# untitled.net
KiCad netlist of a schematic drawn in EAGLE
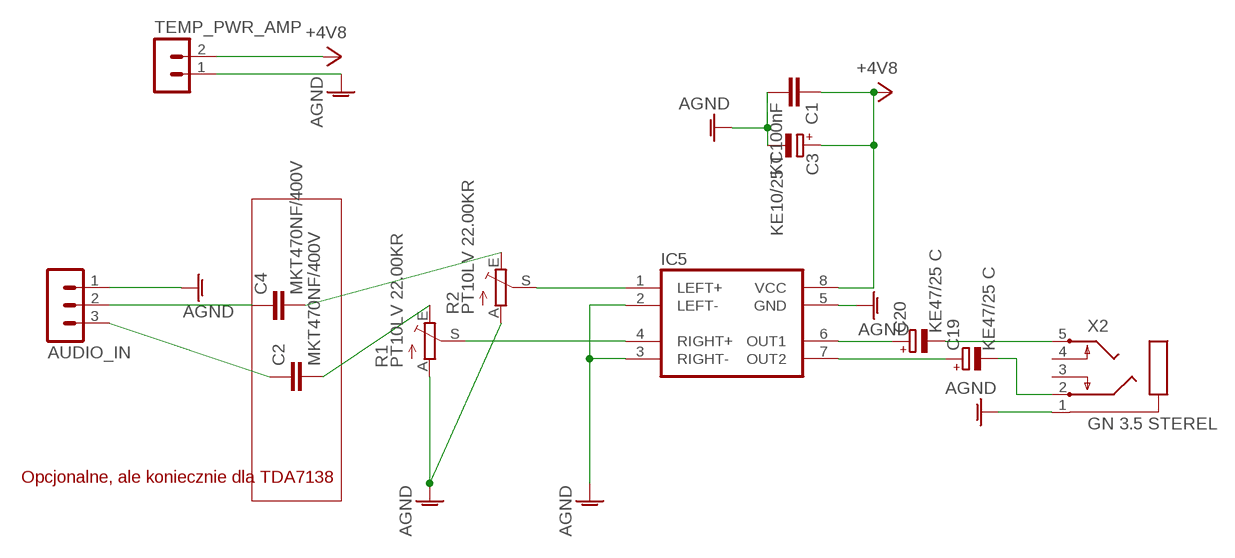
[diagram p0: schematic, sheet 1]

(export (version "E")
  (design (tool "Eeschema 10.0.6"))
  (components
    (comp (ref "AUDIO_IN")
      (value "MA03-1")
      (footprint "eagle-import:MA03-1")
      (fields (field (name "OC_FARNELL") "unknown") (field (name "OC_NEWARK") "unknown"))
      (libsource (lib "eagle-import") (part "MA03-1"))
    )
    (comp (ref "C1")
      (value "KC100nF")
      (footprint "eagle-import:C025-025X050")
      (libsource (lib "eagle-import") (part "C-EU025-025X050"))
    )
    (comp (ref "C2")
      (value "MKT470NF/400V")
      (footprint "eagle-import:C150-091X182")
      (libsource (lib "eagle-import") (part "C-EU150-091X182"))
    )
    (comp (ref "C3")
      (value "KE10/25 T")
      (footprint "eagle-import:TT2D6")
      (libsource (lib "eagle-import") (part "CPOL-EUTT2D6"))
    )
    (comp (ref "C4")
      (value "MKT470NF/400V")
      (footprint "eagle-import:C150-091X182")
      (libsource (lib "eagle-import") (part "C-EU150-091X182"))
    )
    (comp (ref "C19")
      (value "KE47/25 C")
      (footprint "eagle-import:PANASONIC_D")
      (libsource (lib "eagle-import") (part "CPOL-EUD"))
    )
    (comp (ref "C20")
      (value "KE47/25 C")
      (footprint "eagle-import:PANASONIC_D")
      (libsource (lib "eagle-import") (part "CPOL-EUD"))
    )
    (comp (ref "IC5")
      (value "TDA7050")
      (footprint "eagle-import:DIL08")
      (libsource (lib "eagle-import") (part "TDA7050"))
    )
    (comp (ref "R1")
      (value "PT10LV 22.00KR")
      (footprint "eagle-import:CA9V")
      (libsource (lib "eagle-import") (part "TRIM_EU-CA9V"))
    )
    (comp (ref "R2")
      (value "PT10LV 22.00KR")
      (footprint "eagle-import:CA9V")
      (libsource (lib "eagle-import") (part "TRIM_EU-CA9V"))
    )
    (comp (ref "TEMP_PWR_AMP")
      (value "MA02-1")
      (footprint "eagle-import:MA02-1")
      (libsource (lib "eagle-import") (part "MA02-1"))
    )
    (comp (ref "X2")
      (value "GN 3.5 STEREL")
      (footprint "eagle-import:STX3100")
      (libsource (lib "eagle-import") (part "STEREOJACK"))
    )
  )
  (nets
    (net (code "1") (name "+4V8") (class "Default")
      (node (ref "C1") (pin "1") (pinfunction "1_1") (pintype "passive"))
      (node (ref "C3") (pin "+") (pinfunction "+_+") (pintype "passive"))
      (node (ref "IC5") (pin "8") (pinfunction "VCC_8") (pintype "bidirectional"))
      (node (ref "TEMP_PWR_AMP") (pin "2") (pinfunction "2_2") (pintype "passive"))
    )
    (net (code "2") (name "AGND") (class "Default")
      (node (ref "AUDIO_IN") (pin "1") (pinfunction "1_1") (pintype "passive"))
      (node (ref "C1") (pin "2") (pinfunction "2_2") (pintype "passive"))
      (node (ref "C3") (pin "-") (pinfunction "-_-") (pintype "passive"))
      (node (ref "IC5") (pin "2") (pinfunction "LEFT-_2") (pintype "input"))
      (node (ref "IC5") (pin "3") (pinfunction "RIGHT-_3") (pintype "input"))
      (node (ref "IC5") (pin "5") (pinfunction "GND_5") (pintype "bidirectional"))
      (node (ref "R1") (pin "A") (pinfunction "A_A") (pintype "passive"))
      (node (ref "R2") (pin "A") (pinfunction "A_A") (pintype "passive"))
      (node (ref "TEMP_PWR_AMP") (pin "1") (pinfunction "1_1") (pintype "passive"))
      (node (ref "X2") (pin "1") (pinfunction "1_1") (pintype "passive"))
    )
    (net (code "3") (name "Net-(AUDIO_IN-Pad2)") (class "Default")
      (node (ref "AUDIO_IN") (pin "2") (pinfunction "2_2") (pintype "passive"))
      (node (ref "C4") (pin "1") (pinfunction "1_1") (pintype "passive"))
    )
    (net (code "4") (name "Net-(AUDIO_IN-Pad3)") (class "Default")
      (node (ref "AUDIO_IN") (pin "3") (pinfunction "3_3") (pintype "passive"))
      (node (ref "C2") (pin "1") (pinfunction "1_1") (pintype "passive"))
    )
    (net (code "5") (name "Net-(C2-Pad2)") (class "Default")
      (node (ref "C2") (pin "2") (pinfunction "2_2") (pintype "passive"))
      (node (ref "R1") (pin "E") (pinfunction "E_E") (pintype "passive"))
    )
    (net (code "6") (name "Net-(C4-Pad2)") (class "Default")
      (node (ref "C4") (pin "2") (pinfunction "2_2") (pintype "passive"))
      (node (ref "R2") (pin "E") (pinfunction "E_E") (pintype "passive"))
    )
    (net (code "7") (name "Net-(C19-Pad-)") (class "Default")
      (node (ref "C19") (pin "-") (pinfunction "-_-") (pintype "passive"))
      (node (ref "X2") (pin "2") (pinfunction "2_2") (pintype "passive"))
    )
    (net (code "8") (name "Net-(C20-Pad-)") (class "Default")
      (node (ref "C20") (pin "-") (pinfunction "-_-") (pintype "passive"))
      (node (ref "X2") (pin "5") (pinfunction "5_5") (pintype "passive"))
    )
    (net (code "9") (name "Net-(IC5-LEFT+)") (class "Default")
      (node (ref "IC5") (pin "1") (pinfunction "LEFT+_1") (pintype "input"))
      (node (ref "R2") (pin "S") (pinfunction "S_S") (pintype "passive"))
    )
    (net (code "10") (name "Net-(IC5-OUT1)") (class "Default")
      (node (ref "C20") (pin "+") (pinfunction "+_+") (pintype "passive"))
      (node (ref "IC5") (pin "6") (pinfunction "OUT1_6") (pintype "output"))
    )
    (net (code "11") (name "Net-(IC5-OUT2)") (class "Default")
      (node (ref "C19") (pin "+") (pinfunction "+_+") (pintype "passive"))
      (node (ref "IC5") (pin "7") (pinfunction "OUT2_7") (pintype "output"))
    )
    (net (code "12") (name "Net-(IC5-RIGHT+)") (class "Default")
      (node (ref "IC5") (pin "4") (pinfunction "RIGHT+_4") (pintype "input"))
      (node (ref "R1") (pin "S") (pinfunction "S_S") (pintype "passive"))
    )
    (net (code "13") (name "unconnected-(X2-Pad3)") (class "Default")
      (node (ref "X2") (pin "3") (pinfunction "3_3") (pintype "passive"))
    )
    (net (code "14") (name "unconnected-(X2-Pad4)") (class "Default")
      (node (ref "X2") (pin "4") (pinfunction "4_4") (pintype "passive"))
    )
  )
)
